# real-schematic.net
KiCad netlist of a schematic drawn in EAGLE
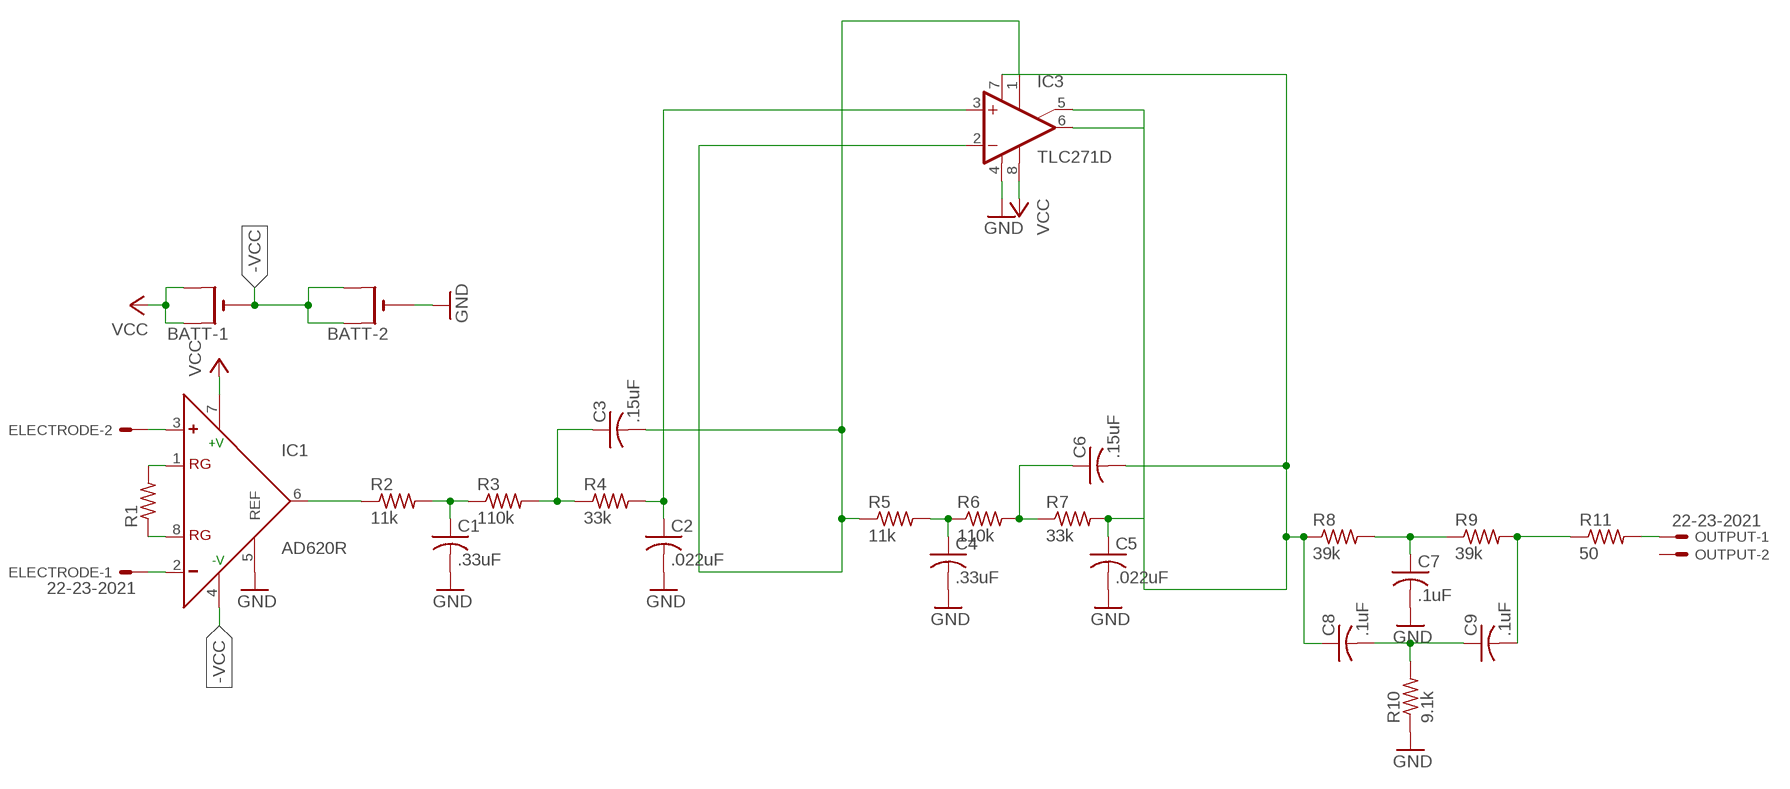
[diagram p0: schematic, sheet 1]

(export (version "E")
  (design (tool "Eeschema 10.0.6"))
  (components
    (comp (ref "BATT-1")
      (value "CR1220SMT")
      (footprint "eagle-import:CR1220-SMD")
      (libsource (lib "eagle-import") (part "CR1220SMT"))
    )
    (comp (ref "BATT-2")
      (value "CR1220SMT")
      (footprint "eagle-import:CR1220-SMD")
      (libsource (lib "eagle-import") (part "CR1220SMT"))
    )
    (comp (ref "C1")
      (value ".33uF")
      (footprint "eagle-import:C0805")
      (libsource (lib "eagle-import") (part "C-USC0805"))
    )
    (comp (ref "C2")
      (value ".022uF")
      (footprint "eagle-import:C0805")
      (libsource (lib "eagle-import") (part "C-USC0805"))
    )
    (comp (ref "C3")
      (value ".15uF")
      (footprint "eagle-import:C0805")
      (libsource (lib "eagle-import") (part "C-USC0805"))
    )
    (comp (ref "C4")
      (value ".33uF")
      (footprint "eagle-import:C0805")
      (libsource (lib "eagle-import") (part "C-USC0805"))
    )
    (comp (ref "C5")
      (value ".022uF")
      (footprint "eagle-import:C0805")
      (libsource (lib "eagle-import") (part "C-USC0805"))
    )
    (comp (ref "C6")
      (value ".15uF")
      (footprint "eagle-import:C0805")
      (libsource (lib "eagle-import") (part "C-USC0805"))
    )
    (comp (ref "C7")
      (value ".1uF")
      (footprint "eagle-import:C0805")
      (libsource (lib "eagle-import") (part "C-USC0805"))
    )
    (comp (ref "C8")
      (value ".1uF")
      (footprint "eagle-import:C0805")
      (libsource (lib "eagle-import") (part "C-USC0805"))
    )
    (comp (ref "C9")
      (value ".1uF")
      (footprint "eagle-import:C0805")
      (libsource (lib "eagle-import") (part "C-USC0805"))
    )
    (comp (ref "ELECTRODE")
      (value "22-23-2021")
      (footprint "eagle-import:22-23-2021")
      (fields (field (name "MF") "MOLEX"))
      (libsource (lib "eagle-import") (part "22-23-2021"))
    )
    (comp (ref "IC1")
      (value "AD620R")
      (footprint "eagle-import:SO8")
      (fields (field (name "MPN") "AD620AR"))
      (libsource (lib "eagle-import") (part "AD620R"))
    )
    (comp (ref "IC3")
      (value "TLC271D")
      (footprint "eagle-import:SO08")
      (libsource (lib "eagle-import") (part "TLC271D"))
    )
    (comp (ref "OUTPUT")
      (value "22-23-2021")
      (footprint "eagle-import:22-23-2021")
      (fields (field (name "MF") "MOLEX"))
      (libsource (lib "eagle-import") (part "22-23-2021"))
    )
    (comp (ref "R1")
      (value "R-US_R0805")
      (footprint "eagle-import:R0805")
      (libsource (lib "eagle-import") (part "R-US_R0805"))
    )
    (comp (ref "R2")
      (value "11k")
      (footprint "eagle-import:R0805")
      (libsource (lib "eagle-import") (part "R-US_R0805"))
    )
    (comp (ref "R3")
      (value "110k")
      (footprint "eagle-import:R0805")
      (libsource (lib "eagle-import") (part "R-US_R0805"))
    )
    (comp (ref "R4")
      (value "33k")
      (footprint "eagle-import:R0805")
      (libsource (lib "eagle-import") (part "R-US_R0805"))
    )
    (comp (ref "R5")
      (value "11k")
      (footprint "eagle-import:R0805")
      (libsource (lib "eagle-import") (part "R-US_R0805"))
    )
    (comp (ref "R6")
      (value "110k")
      (footprint "eagle-import:R0805")
      (libsource (lib "eagle-import") (part "R-US_R0805"))
    )
    (comp (ref "R7")
      (value "33k")
      (footprint "eagle-import:R0805")
      (libsource (lib "eagle-import") (part "R-US_R0805"))
    )
    (comp (ref "R8")
      (value "39k")
      (footprint "eagle-import:R0805")
      (libsource (lib "eagle-import") (part "R-US_R0805"))
    )
    (comp (ref "R9")
      (value "39k")
      (footprint "eagle-import:R0805")
      (libsource (lib "eagle-import") (part "R-US_R0805"))
    )
    (comp (ref "R10")
      (value "9.1k")
      (footprint "eagle-import:R0805")
      (libsource (lib "eagle-import") (part "R-US_R0805"))
    )
    (comp (ref "R11")
      (value "50")
      (footprint "eagle-import:R0805")
      (libsource (lib "eagle-import") (part "R-US_R0805"))
    )
  )
  (nets
    (net (code "1") (name "-VCC") (class "Default")
      (node (ref "BATT-1") (pin "-") (pinfunction "-_-") (pintype "passive"))
      (node (ref "BATT-2") (pin "+$1") (pinfunction "+_+$1") (pintype "passive"))
      (node (ref "BATT-2") (pin "+$2") (pinfunction "+1_+$2") (pintype "passive"))
      (node (ref "IC1") (pin "4") (pinfunction "-V_4") (pintype "power_in"))
    )
    (net (code "2") (name "GND") (class "Default")
      (node (ref "BATT-2") (pin "-") (pinfunction "-_-") (pintype "passive"))
      (node (ref "C1") (pin "2") (pinfunction "2_2") (pintype "passive"))
      (node (ref "C2") (pin "2") (pinfunction "2_2") (pintype "passive"))
      (node (ref "C4") (pin "2") (pinfunction "2_2") (pintype "passive"))
      (node (ref "C5") (pin "2") (pinfunction "2_2") (pintype "passive"))
      (node (ref "C7") (pin "2") (pinfunction "2_2") (pintype "passive"))
      (node (ref "IC1") (pin "5") (pinfunction "REF_5") (pintype "passive"))
      (node (ref "IC3") (pin "4") (pinfunction "V-_4") (pintype "power_in"))
      (node (ref "R10") (pin "1") (pinfunction "1_1") (pintype "passive"))
    )
    (net (code "3") (name "Net-(C1-Pad1)") (class "Default")
      (node (ref "C1") (pin "1") (pinfunction "1_1") (pintype "passive"))
      (node (ref "R2") (pin "2") (pinfunction "2_2") (pintype "passive"))
      (node (ref "R3") (pin "1") (pinfunction "1_1") (pintype "passive"))
    )
    (net (code "4") (name "Net-(C3-Pad1)") (class "Default")
      (node (ref "C3") (pin "1") (pinfunction "1_1") (pintype "passive"))
      (node (ref "R3") (pin "2") (pinfunction "2_2") (pintype "passive"))
      (node (ref "R4") (pin "1") (pinfunction "1_1") (pintype "passive"))
    )
    (net (code "5") (name "Net-(C4-Pad1)") (class "Default")
      (node (ref "C4") (pin "1") (pinfunction "1_1") (pintype "passive"))
      (node (ref "R5") (pin "2") (pinfunction "2_2") (pintype "passive"))
      (node (ref "R6") (pin "1") (pinfunction "1_1") (pintype "passive"))
    )
    (net (code "6") (name "Net-(C6-Pad1)") (class "Default")
      (node (ref "C6") (pin "1") (pinfunction "1_1") (pintype "passive"))
      (node (ref "R6") (pin "2") (pinfunction "2_2") (pintype "passive"))
      (node (ref "R7") (pin "1") (pinfunction "1_1") (pintype "passive"))
    )
    (net (code "7") (name "Net-(C7-Pad1)") (class "Default")
      (node (ref "C7") (pin "1") (pinfunction "1_1") (pintype "passive"))
      (node (ref "R8") (pin "2") (pinfunction "2_2") (pintype "passive"))
      (node (ref "R9") (pin "1") (pinfunction "1_1") (pintype "passive"))
    )
    (net (code "8") (name "Net-(C8-Pad2)") (class "Default")
      (node (ref "C8") (pin "2") (pinfunction "2_2") (pintype "passive"))
      (node (ref "C9") (pin "1") (pinfunction "1_1") (pintype "passive"))
      (node (ref "R10") (pin "2") (pinfunction "2_2") (pintype "passive"))
    )
    (net (code "9") (name "Net-(C9-Pad2)") (class "Default")
      (node (ref "C9") (pin "2") (pinfunction "2_2") (pintype "passive"))
      (node (ref "R11") (pin "1") (pinfunction "1_1") (pintype "passive"))
      (node (ref "R9") (pin "2") (pinfunction "2_2") (pintype "passive"))
    )
    (net (code "10") (name "Net-(ELECTRODEA-S)") (class "Default")
      (node (ref "ELECTRODE") (pin "1") (pinfunction "S_1") (pintype "passive"))
      (node (ref "IC1") (pin "2") (pinfunction "-_2") (pintype "input"))
    )
    (net (code "11") (name "Net-(ELECTRODEB-S)") (class "Default")
      (node (ref "ELECTRODE") (pin "2") (pinfunction "S_2") (pintype "passive"))
      (node (ref "IC1") (pin "3") (pinfunction "+_3") (pintype "input"))
    )
    (net (code "12") (name "Net-(IC1-OUT)") (class "Default")
      (node (ref "IC1") (pin "6") (pinfunction "OUT_6") (pintype "output"))
      (node (ref "R2") (pin "1") (pinfunction "1_1") (pintype "passive"))
    )
    (net (code "13") (name "Net-(IC1-RG-Pad1)") (class "Default")
      (node (ref "IC1") (pin "1") (pinfunction "RG_1") (pintype "passive"))
      (node (ref "R1") (pin "2") (pinfunction "2_2") (pintype "passive"))
    )
    (net (code "14") (name "Net-(IC1-RG-Pad8)") (class "Default")
      (node (ref "IC1") (pin "8") (pinfunction "RG_8") (pintype "passive"))
      (node (ref "R1") (pin "1") (pinfunction "1_1") (pintype "passive"))
    )
    (net (code "15") (name "Net-(IC3-+IN)") (class "Default")
      (node (ref "C2") (pin "1") (pinfunction "1_1") (pintype "passive"))
      (node (ref "IC3") (pin "3") (pinfunction "+IN_3") (pintype "input"))
      (node (ref "R4") (pin "2") (pinfunction "2_2") (pintype "passive"))
    )
    (net (code "16") (name "Net-(IC3--IN)") (class "Default")
      (node (ref "C3") (pin "2") (pinfunction "2_2") (pintype "passive"))
      (node (ref "IC3") (pin "1") (pinfunction "ON1_1") (pintype "passive"))
      (node (ref "IC3") (pin "2") (pinfunction "-IN_2") (pintype "input"))
      (node (ref "R5") (pin "1") (pinfunction "1_1") (pintype "passive"))
    )
    (net (code "17") (name "Net-(IC3-ON2)") (class "Default")
      (node (ref "C5") (pin "1") (pinfunction "1_1") (pintype "passive"))
      (node (ref "IC3") (pin "5") (pinfunction "ON2_5") (pintype "passive"))
      (node (ref "R7") (pin "2") (pinfunction "2_2") (pintype "passive"))
    )
    (net (code "18") (name "Net-(IC3-OUT)") (class "Default")
      (node (ref "C6") (pin "2") (pinfunction "2_2") (pintype "passive"))
      (node (ref "C8") (pin "1") (pinfunction "1_1") (pintype "passive"))
      (node (ref "IC3") (pin "6") (pinfunction "OUT_6") (pintype "output"))
      (node (ref "IC3") (pin "7") (pinfunction "V+_7") (pintype "power_in"))
      (node (ref "R8") (pin "1") (pinfunction "1_1") (pintype "passive"))
    )
    (net (code "19") (name "Net-(OUTPUTA-S)") (class "Default")
      (node (ref "OUTPUT") (pin "1") (pinfunction "S_1") (pintype "passive"))
      (node (ref "R11") (pin "2") (pinfunction "2_2") (pintype "passive"))
    )
    (net (code "20") (name "VCC") (class "Default")
      (node (ref "BATT-1") (pin "+$1") (pinfunction "+_+$1") (pintype "passive"))
      (node (ref "BATT-1") (pin "+$2") (pinfunction "+1_+$2") (pintype "passive"))
      (node (ref "IC1") (pin "7") (pinfunction "+V_7") (pintype "power_in"))
      (node (ref "IC3") (pin "8") (pinfunction "OPT_8") (pintype "passive"))
    )
    (net (code "21") (name "unconnected-(OUTPUTB-S-Pad2)") (class "Default")
      (node (ref "OUTPUT") (pin "2") (pinfunction "S_2") (pintype "passive"))
    )
  )
)
